# Micro.net
KiCad netlist of a schematic drawn in Altium Designer
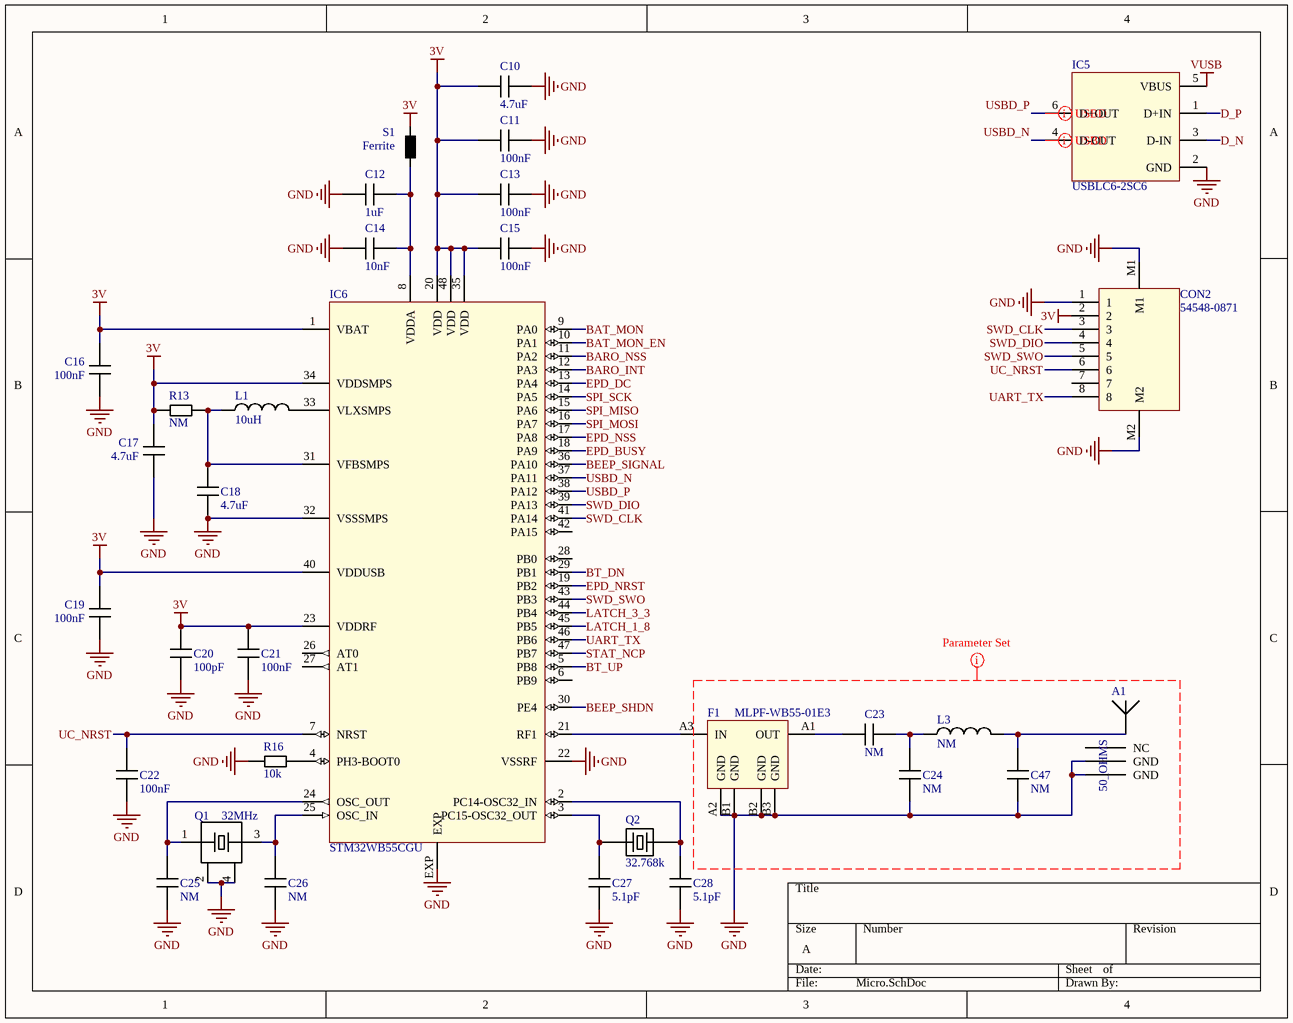
[diagram p0: Micro.SchDoc]

(export (version "E")
  (design (tool "Eeschema 10.0.6"))
  (components
    (comp (ref "A1")
      (value "50_OHMS")
      (footprint "2450AT42E0100")
      (description "RF ANT 900MHZ HELICAL SOLDER SMD")
      (fields (field (name "Comment") "2450AT42E0100"))
      (libsource (lib "Antenna") (part "2450AT42E0100"))
    )
    (comp (ref "C10")
      (value "4.7uF")
      (footprint "C0402")
      (description "X7T 0402 10% 6.3V AEC-Q200")
      (fields (field (name "Comment") "4.7uF (0402) AEC-Q200"))
      (libsource (lib "Cap") (part "4.7uF (0402) AEC-Q200"))
    )
    (comp (ref "C11")
      (value "100nF")
      (footprint "C0402")
      (description "X7R 0402 10% 50V AEC-Q200")
      (fields (field (name "Comment") "100nF (0402) AEC-Q200"))
      (libsource (lib "Cap") (part "100nF (0402) AEC-Q200"))
    )
    (comp (ref "C12")
      (value "1uF")
      (footprint "C0402")
      (description "X7S 10% 0402 16V")
      (fields (field (name "Comment") "1uF (0402)"))
      (libsource (lib "Cap") (part "1uF (0402)"))
    )
    (comp (ref "C13")
      (value "100nF")
      (footprint "C0402")
      (description "X7R 0402 10% 50V AEC-Q200")
      (fields (field (name "Comment") "100nF (0402) AEC-Q200"))
      (libsource (lib "Cap") (part "100nF (0402) AEC-Q200"))
    )
    (comp (ref "C14")
      (value "10nF")
      (footprint "C0402")
      (description "X7R 0402 10% 50V AEC-Q200")
      (fields (field (name "Comment") "10nF (0402) AEC-Q200"))
      (libsource (lib "Cap") (part "10nF (0402) AEC-Q200"))
    )
    (comp (ref "C15")
      (value "100nF")
      (footprint "C0402")
      (description "X7R 0402 10% 50V AEC-Q200")
      (fields (field (name "Comment") "100nF (0402) AEC-Q200"))
      (libsource (lib "Cap") (part "100nF (0402) AEC-Q200"))
    )
    (comp (ref "C16")
      (value "100nF")
      (footprint "C0402")
      (description "X7R 0402 10% 50V AEC-Q200")
      (fields (field (name "Comment") "100nF (0402) AEC-Q200"))
      (libsource (lib "Cap") (part "100nF (0402) AEC-Q200"))
    )
    (comp (ref "C17")
      (value "4.7uF")
      (footprint "C0402")
      (description "X7T 0402 10% 6.3V AEC-Q200")
      (fields (field (name "Comment") "4.7uF (0402) AEC-Q200"))
      (libsource (lib "Cap") (part "4.7uF (0402) AEC-Q200"))
    )
    (comp (ref "C18")
      (value "4.7uF")
      (footprint "C0402")
      (description "X7T 0402 10% 6.3V AEC-Q200")
      (fields (field (name "Comment") "4.7uF (0402) AEC-Q200"))
      (libsource (lib "Cap") (part "4.7uF (0402) AEC-Q200"))
    )
    (comp (ref "C19")
      (value "100nF")
      (footprint "C0402")
      (description "X7R 0402 10% 50V AEC-Q200")
      (fields (field (name "Comment") "100nF (0402) AEC-Q200"))
      (libsource (lib "Cap") (part "100nF (0402) AEC-Q200"))
    )
    (comp (ref "C20")
      (value "100pF")
      (footprint "C0402")
      (description "NP0 0402 5% 50V AEC-Q200")
      (fields (field (name "Comment") "100pF (0402) AEC-Q200"))
      (libsource (lib "Cap") (part "100pF (0402) AEC-Q200"))
    )
    (comp (ref "C21")
      (value "100nF")
      (footprint "C0402")
      (description "X7R 0402 10% 50V AEC-Q200")
      (fields (field (name "Comment") "100nF (0402) AEC-Q200"))
      (libsource (lib "Cap") (part "100nF (0402) AEC-Q200"))
    )
    (comp (ref "C22")
      (value "100nF")
      (footprint "C0402")
      (description "X7R 0402 10% 50V AEC-Q200")
      (fields (field (name "Comment") "100nF (0402) AEC-Q200"))
      (libsource (lib "Cap") (part "100nF (0402) AEC-Q200"))
    )
    (comp (ref "C23")
      (value "NM")
      (footprint "C0402 (NM)")
      (fields (field (name "Comment") "NM (0402)"))
      (libsource (lib "Cap") (part "NM (0402)"))
    )
    (comp (ref "C24")
      (value "NM")
      (footprint "C0402 (NM)")
      (fields (field (name "Comment") "NM (0402)"))
      (libsource (lib "Cap") (part "NM (0402)"))
    )
    (comp (ref "C25")
      (value "NM")
      (footprint "C0402 (NM)")
      (fields (field (name "Comment") "NM (0402)"))
      (libsource (lib "Cap") (part "NM (0402)"))
    )
    (comp (ref "C26")
      (value "NM")
      (footprint "C0402 (NM)")
      (fields (field (name "Comment") "NM (0402)"))
      (libsource (lib "Cap") (part "NM (0402)"))
    )
    (comp (ref "C27")
      (value "5.1pF")
      (footprint "C0402")
      (description "NP0 0402 5% 50V AEC-Q200")
      (fields (field (name "Comment") "5.1pF (0402) AEC-Q200"))
      (libsource (lib "Cap") (part "5.1pF (0402) AEC-Q200"))
    )
    (comp (ref "C28")
      (value "5.1pF")
      (footprint "C0402")
      (description "NP0 0402 5% 50V AEC-Q200")
      (fields (field (name "Comment") "5.1pF (0402) AEC-Q200"))
      (libsource (lib "Cap") (part "5.1pF (0402) AEC-Q200"))
    )
    (comp (ref "C47")
      (value "NM")
      (footprint "C0402 (NM)")
      (fields (field (name "Comment") "NM (0402)"))
      (libsource (lib "Cap") (part "NM (0402)"))
    )
    (comp (ref "CON2")
      (value "54548-0871")
      (footprint "54548-0871")
      (description "Connecteur FFC/FPC, Right-Angle, Surface Mount, ZIF, Bottom Contact\r\nStyle, 30 Circuits")
      (libsource (lib "ConnecteurAutre") (part "54548-0871"))
    )
    (comp (ref "F1")
      (value "MLPF-WB55-01E3")
      (footprint "MLPF-WB-01E3")
      (description "2.4 GHz low pass filter matched to STM32WB55C")
      (libsource (lib "Antenna") (part "MLPF-WB55-01E3"))
    )
    (comp (ref "IC5")
      (value "USBLC6-2SC6")
      (footprint "SOT23-6")
      (fields (field (name "Comment") "USBLC6-2"))
      (libsource (lib "USB") (part "USBLC6-2"))
    )
    (comp (ref "IC6")
      (value "STM32WB55CGU")
      (footprint "UFQFPN48")
      (libsource (lib "Transceiver") (part "STM32WB55CGU"))
    )
    (comp (ref "L1")
      (value "10uH")
      (footprint "2.5x2 (2512)")
      (description "20% 2.5x2 semi-blindé AEC-Q200")
      (fields (field (name "Comment") "10uH (2.5x2) AEC-Q200"))
      (libsource (lib "Inductance") (part "10uH (2.5x2) AEC-Q200"))
    )
    (comp (ref "L3")
      (value "NM")
      (footprint "S0402 (NM)")
      (fields (field (name "Comment") "NM (0402)"))
      (libsource (lib "Inductance") (part "NM (0402)"))
    )
    (comp (ref "Q1")
      (value "32MHz")
      (footprint "2.0x1.6 - ECS-320-8-47Q")
      (description "Quartz 32MHz")
      (fields (field (name "Comment") "ECS-320-8-47Q-CES-TR"))
      (libsource (lib "Oscillateur") (part "ECS-320-8-47Q-CES-TR"))
    )
    (comp (ref "Q2")
      (value "32.768k")
      (footprint "3.2x1.5")
      (description "Cristal, 32.768 kHz, CMS, 3.2mm x 1.5mm AEC-Q200")
      (fields (field (name "Comment") "ECS-.327-12.5-34QCS-TR"))
      (libsource (lib "Oscillateur") (part "ECS-.327-12.5-34QCS-TR"))
    )
    (comp (ref "R13")
      (value "NM")
      (footprint "R0402 (NM)")
      (fields (field (name "Comment") "NM (0402)"))
      (libsource (lib "Res") (part "NM (0402)"))
    )
    (comp (ref "R16")
      (value "10k")
      (footprint "R0402")
      (description "1% 0402 0.1W 100ppm AEC-Q200")
      (fields (field (name "Comment") "10k (0402) AEC-Q200"))
      (libsource (lib "Res") (part "10k (0402) AEC-Q200"))
    )
    (comp (ref "S1")
      (value "Ferrite")
      (footprint "0402 (FERRITE)")
      (description "Perle de ferrite AEC-Q200")
      (fields (field (name "Comment") "Ferrite (0402) 1k AEC-Q200"))
      (libsource (lib "LED_TH_VAR_FER") (part "Ferrite (0402) 1k AEC-Q200"))
    )
  )
  (nets
    (net (code "1") (name "/BARO_INT") (class "Default")
      (node (ref "IC6") (pin "12") (pinfunction "PA3_12") (pintype "bidirectional"))
    )
    (net (code "2") (name "/BARO_NSS") (class "Default")
      (node (ref "IC6") (pin "11") (pinfunction "PA2_11") (pintype "bidirectional"))
    )
    (net (code "3") (name "/BAT_MON") (class "Default")
      (node (ref "IC6") (pin "9") (pinfunction "PA0_9") (pintype "bidirectional"))
    )
    (net (code "4") (name "/BAT_MON_EN") (class "Default")
      (node (ref "IC6") (pin "10") (pinfunction "PA1_10") (pintype "bidirectional"))
    )
    (net (code "5") (name "/BEEP_SHDN") (class "Default")
      (node (ref "IC6") (pin "30") (pinfunction "PE4_30") (pintype "bidirectional"))
    )
    (net (code "6") (name "/BEEP_SIGNAL") (class "Default")
      (node (ref "IC6") (pin "36") (pinfunction "PA10_36") (pintype "bidirectional"))
    )
    (net (code "7") (name "/BT_DN") (class "Default")
      (node (ref "IC6") (pin "29") (pinfunction "PB1_29") (pintype "bidirectional"))
    )
    (net (code "8") (name "/BT_UP") (class "Default")
      (node (ref "IC6") (pin "5") (pinfunction "PB8_5") (pintype "bidirectional"))
    )
    (net (code "9") (name "/D_N") (class "Default")
      (node (ref "IC5") (pin "3") (pinfunction "D-IN_3") (pintype "passive"))
    )
    (net (code "10") (name "/D_P") (class "Default")
      (node (ref "IC5") (pin "1") (pinfunction "D+IN_1") (pintype "passive"))
    )
    (net (code "11") (name "/EPD_BUSY") (class "Default")
      (node (ref "IC6") (pin "18") (pinfunction "PA9_18") (pintype "bidirectional"))
    )
    (net (code "12") (name "/EPD_DC") (class "Default")
      (node (ref "IC6") (pin "13") (pinfunction "PA4_13") (pintype "bidirectional"))
    )
    (net (code "13") (name "/EPD_NRST") (class "Default")
      (node (ref "IC6") (pin "19") (pinfunction "PB2_19") (pintype "bidirectional"))
    )
    (net (code "14") (name "/EPD_NSS") (class "Default")
      (node (ref "IC6") (pin "17") (pinfunction "PA8_17") (pintype "bidirectional"))
    )
    (net (code "15") (name "/LATCH_1_8") (class "Default")
      (node (ref "IC6") (pin "45") (pinfunction "PB5_45") (pintype "bidirectional"))
    )
    (net (code "16") (name "/LATCH_3_3") (class "Default")
      (node (ref "IC6") (pin "44") (pinfunction "PB4_44") (pintype "bidirectional"))
    )
    (net (code "17") (name "/SPI_MISO") (class "Default")
      (node (ref "IC6") (pin "15") (pinfunction "PA6_15") (pintype "bidirectional"))
    )
    (net (code "18") (name "/SPI_MOSI") (class "Default")
      (node (ref "IC6") (pin "16") (pinfunction "PA7_16") (pintype "bidirectional"))
    )
    (net (code "19") (name "/SPI_SCK") (class "Default")
      (node (ref "IC6") (pin "14") (pinfunction "PA5_14") (pintype "bidirectional"))
    )
    (net (code "20") (name "/STAT_NCP") (class "Default")
      (node (ref "IC6") (pin "47") (pinfunction "PB7_47") (pintype "bidirectional"))
    )
    (net (code "21") (name "/SWD_CLK") (class "Default")
      (node (ref "CON2") (pin "3") (pinfunction "3_3") (pintype "power_in"))
      (node (ref "IC6") (pin "41") (pinfunction "PA14_41") (pintype "bidirectional"))
    )
    (net (code "22") (name "/SWD_DIO") (class "Default")
      (node (ref "CON2") (pin "4") (pinfunction "4_4") (pintype "power_in"))
      (node (ref "IC6") (pin "39") (pinfunction "PA13_39") (pintype "bidirectional"))
    )
    (net (code "23") (name "/SWD_SWO") (class "Default")
      (node (ref "CON2") (pin "5") (pinfunction "5_5") (pintype "power_in"))
      (node (ref "IC6") (pin "43") (pinfunction "PB3_43") (pintype "bidirectional"))
    )
    (net (code "24") (name "/UART_TX") (class "Default")
      (node (ref "CON2") (pin "8") (pinfunction "8_8") (pintype "power_in"))
      (node (ref "IC6") (pin "46") (pinfunction "PB6_46") (pintype "bidirectional"))
    )
    (net (code "25") (name "/UC_NRST") (class "Default")
      (node (ref "C22") (pin "1") (pinfunction "1_1") (pintype "passive"))
      (node (ref "CON2") (pin "6") (pinfunction "6_6") (pintype "power_in"))
      (node (ref "IC6") (pin "7") (pinfunction "NRST_7") (pintype "bidirectional"))
    )
    (net (code "26") (name "/USBD_N") (class "Default")
      (node (ref "IC5") (pin "4") (pinfunction "D-OUT_4") (pintype "passive"))
      (node (ref "IC6") (pin "37") (pinfunction "PA11_37") (pintype "bidirectional"))
    )
    (net (code "27") (name "/USBD_P") (class "Default")
      (node (ref "IC5") (pin "6") (pinfunction "D+OUT_6") (pintype "passive"))
      (node (ref "IC6") (pin "38") (pinfunction "PA12_38") (pintype "bidirectional"))
    )
    (net (code "28") (name "3V") (class "Default")
      (node (ref "C10") (pin "2") (pinfunction "2_2") (pintype "passive"))
      (node (ref "C11") (pin "1") (pinfunction "1_1") (pintype "passive"))
      (node (ref "C13") (pin "1") (pinfunction "1_1") (pintype "passive"))
      (node (ref "C15") (pin "1") (pinfunction "1_1") (pintype "passive"))
      (node (ref "C16") (pin "1") (pinfunction "1_1") (pintype "passive"))
      (node (ref "C17") (pin "2") (pinfunction "2_2") (pintype "passive"))
      (node (ref "C19") (pin "1") (pinfunction "1_1") (pintype "passive"))
      (node (ref "C20") (pin "1") (pinfunction "1_1") (pintype "passive"))
      (node (ref "C21") (pin "1") (pinfunction "1_1") (pintype "passive"))
      (node (ref "CON2") (pin "2") (pinfunction "2_2") (pintype "power_in"))
      (node (ref "IC6") (pin "1") (pinfunction "VBAT_1") (pintype "power_in"))
      (node (ref "IC6") (pin "20") (pinfunction "VDD_20") (pintype "power_in"))
      (node (ref "IC6") (pin "23") (pinfunction "VDDRF_23") (pintype "power_in"))
      (node (ref "IC6") (pin "34") (pinfunction "VDDSMPS_34") (pintype "power_in"))
      (node (ref "IC6") (pin "35") (pinfunction "VDD_35") (pintype "power_in"))
      (node (ref "IC6") (pin "40") (pinfunction "VDDUSB_40") (pintype "power_in"))
      (node (ref "IC6") (pin "48") (pinfunction "VDD_48") (pintype "power_in"))
      (node (ref "R13") (pin "1") (pinfunction "1_1") (pintype "passive"))
      (node (ref "S1") (pin "2") (pinfunction "2_2") (pintype "passive"))
    )
    (net (code "29") (name "GND") (class "Default")
      (node (ref "A1") (pin "3") (pinfunction "GND_3") (pintype "passive"))
      (node (ref "A1") (pin "4") (pinfunction "GND_4") (pintype "passive"))
      (node (ref "C10") (pin "1") (pinfunction "1_1") (pintype "passive"))
      (node (ref "C11") (pin "2") (pinfunction "2_2") (pintype "passive"))
      (node (ref "C12") (pin "1") (pinfunction "1_1") (pintype "passive"))
      (node (ref "C13") (pin "2") (pinfunction "2_2") (pintype "passive"))
      (node (ref "C14") (pin "2") (pinfunction "2_2") (pintype "passive"))
      (node (ref "C15") (pin "2") (pinfunction "2_2") (pintype "passive"))
      (node (ref "C16") (pin "2") (pinfunction "2_2") (pintype "passive"))
      (node (ref "C17") (pin "1") (pinfunction "1_1") (pintype "passive"))
      (node (ref "C18") (pin "1") (pinfunction "1_1") (pintype "passive"))
      (node (ref "C19") (pin "2") (pinfunction "2_2") (pintype "passive"))
      (node (ref "C20") (pin "2") (pinfunction "2_2") (pintype "passive"))
      (node (ref "C21") (pin "2") (pinfunction "2_2") (pintype "passive"))
      (node (ref "C22") (pin "2") (pinfunction "2_2") (pintype "passive"))
      (node (ref "C24") (pin "2") (pinfunction "2_2") (pintype "passive"))
      (node (ref "C25") (pin "2") (pinfunction "2_2") (pintype "passive"))
      (node (ref "C26") (pin "2") (pinfunction "2_2") (pintype "passive"))
      (node (ref "C27") (pin "2") (pinfunction "2_2") (pintype "passive"))
      (node (ref "C28") (pin "2") (pinfunction "2_2") (pintype "passive"))
      (node (ref "C47") (pin "2") (pinfunction "2_2") (pintype "passive"))
      (node (ref "CON2") (pin "1") (pinfunction "1_1") (pintype "power_in"))
      (node (ref "CON2") (pin "M1") (pinfunction "M1_M1") (pintype "power_in"))
      (node (ref "CON2") (pin "M2") (pinfunction "M2_M2") (pintype "power_in"))
      (node (ref "F1") (pin "A2") (pinfunction "GND_A2") (pintype "passive"))
      (node (ref "F1") (pin "B1") (pinfunction "GND_B1") (pintype "passive"))
      (node (ref "F1") (pin "B2") (pinfunction "GND_B2") (pintype "passive"))
      (node (ref "F1") (pin "B3") (pinfunction "GND_B3") (pintype "passive"))
      (node (ref "IC5") (pin "2") (pinfunction "GND_2") (pintype "passive"))
      (node (ref "IC6") (pin "22") (pinfunction "VSSRF_22") (pintype "power_in"))
      (node (ref "IC6") (pin "32") (pinfunction "VSSSMPS_32") (pintype "power_in"))
      (node (ref "IC6") (pin "EXP") (pinfunction "EXP_EXP") (pintype "power_in"))
      (node (ref "Q1") (pin "2") (pintype "passive"))
      (node (ref "Q1") (pin "4") (pintype "passive"))
      (node (ref "R16") (pin "1") (pinfunction "1_1") (pintype "passive"))
    )
    (net (code "30") (name "Net-(A1-Pad1)") (class "Default")
      (node (ref "A1") (pin "1") (pinfunction "1_1") (pintype "passive"))
      (node (ref "C47") (pin "1") (pinfunction "1_1") (pintype "passive"))
      (node (ref "L3") (pin "2") (pinfunction "2_2") (pintype "passive"))
    )
    (net (code "31") (name "Net-(C23-Pad2)") (class "Default")
      (node (ref "C23") (pin "2") (pinfunction "2_2") (pintype "passive"))
      (node (ref "C24") (pin "1") (pinfunction "1_1") (pintype "passive"))
      (node (ref "L3") (pin "1") (pinfunction "1_1") (pintype "passive"))
    )
    (net (code "32") (name "Net-(F1-IN)") (class "Default")
      (node (ref "F1") (pin "A3") (pinfunction "IN_A3") (pintype "passive"))
      (node (ref "IC6") (pin "21") (pinfunction "RF1_21") (pintype "bidirectional"))
    )
    (net (code "33") (name "Net-(F1-OUT)") (class "Default")
      (node (ref "C23") (pin "1") (pinfunction "1_1") (pintype "passive"))
      (node (ref "F1") (pin "A1") (pinfunction "OUT_A1") (pintype "passive"))
    )
    (net (code "34") (name "Net-(IC6-OSC_IN)") (class "Default")
      (node (ref "C26") (pin "1") (pinfunction "1_1") (pintype "passive"))
      (node (ref "IC6") (pin "25") (pinfunction "OSC_IN_25") (pintype "input"))
      (node (ref "Q1") (pin "3") (pinfunction "GND_3") (pintype "passive"))
    )
    (net (code "35") (name "Net-(IC6-OSC_OUT)") (class "Default")
      (node (ref "C25") (pin "1") (pinfunction "1_1") (pintype "passive"))
      (node (ref "IC6") (pin "24") (pinfunction "OSC_OUT_24") (pintype "output"))
      (node (ref "Q1") (pin "1") (pinfunction "NC_1") (pintype "passive"))
    )
    (net (code "36") (name "Net-(IC6-PC14-OSC32_IN)") (class "Default")
      (node (ref "C28") (pin "1") (pinfunction "1_1") (pintype "passive"))
      (node (ref "IC6") (pin "2") (pinfunction "PC14-OSC32_IN_2") (pintype "bidirectional"))
      (node (ref "Q2") (pin "2") (pintype "passive"))
    )
    (net (code "37") (name "Net-(IC6-PC15-OSC32_OUT)") (class "Default")
      (node (ref "C27") (pin "1") (pinfunction "1_1") (pintype "passive"))
      (node (ref "IC6") (pin "3") (pinfunction "PC15-OSC32_OUT_3") (pintype "bidirectional"))
      (node (ref "Q2") (pin "1") (pintype "passive"))
    )
    (net (code "38") (name "Net-(IC6-PH3-BOOT0)") (class "Default")
      (node (ref "IC6") (pin "4") (pinfunction "PH3-BOOT0_4") (pintype "bidirectional"))
      (node (ref "R16") (pin "2") (pinfunction "2_2") (pintype "passive"))
    )
    (net (code "39") (name "Net-(IC6-VDDA)") (class "Default")
      (node (ref "C12") (pin "2") (pinfunction "2_2") (pintype "passive"))
      (node (ref "C14") (pin "1") (pinfunction "1_1") (pintype "passive"))
      (node (ref "IC6") (pin "8") (pinfunction "VDDA_8") (pintype "power_in"))
      (node (ref "S1") (pin "1") (pinfunction "1_1") (pintype "passive"))
    )
    (net (code "40") (name "Net-(IC6-VFBSMPS)") (class "Default")
      (node (ref "C18") (pin "2") (pinfunction "2_2") (pintype "passive"))
      (node (ref "IC6") (pin "31") (pinfunction "VFBSMPS_31") (pintype "power_in"))
      (node (ref "L1") (pin "1") (pinfunction "1_1") (pintype "passive"))
      (node (ref "R13") (pin "2") (pinfunction "2_2") (pintype "passive"))
    )
    (net (code "41") (name "Net-(IC6-VLXSMPS)") (class "Default")
      (node (ref "IC6") (pin "33") (pinfunction "VLXSMPS_33") (pintype "power_in"))
      (node (ref "L1") (pin "2") (pinfunction "2_2") (pintype "passive"))
    )
    (net (code "42") (name "VUSB") (class "Default")
      (node (ref "IC5") (pin "5") (pinfunction "VBUS_5") (pintype "passive"))
    )
    (net (code "43") (name "unconnected-(A1-NC-Pad2)") (class "Default")
      (node (ref "A1") (pin "2") (pinfunction "NC_2") (pintype "passive"))
    )
    (net (code "44") (name "unconnected-(CON2-Pad7)") (class "Default")
      (node (ref "CON2") (pin "7") (pinfunction "7_7") (pintype "power_in"))
    )
    (net (code "45") (name "unconnected-(IC6-AT0-Pad26)") (class "Default")
      (node (ref "IC6") (pin "26") (pinfunction "AT0_26") (pintype "output"))
    )
    (net (code "46") (name "unconnected-(IC6-AT1-Pad27)") (class "Default")
      (node (ref "IC6") (pin "27") (pinfunction "AT1_27") (pintype "output"))
    )
    (net (code "47") (name "unconnected-(IC6-PA15-Pad42)") (class "Default")
      (node (ref "IC6") (pin "42") (pinfunction "PA15_42") (pintype "bidirectional"))
    )
    (net (code "48") (name "unconnected-(IC6-PB0-Pad28)") (class "Default")
      (node (ref "IC6") (pin "28") (pinfunction "PB0_28") (pintype "bidirectional"))
    )
    (net (code "49") (name "unconnected-(IC6-PB9-Pad6)") (class "Default")
      (node (ref "IC6") (pin "6") (pinfunction "PB9_6") (pintype "bidirectional"))
    )
  )
)
